# MCU.net
KiCad netlist of a schematic drawn in Altium Designer
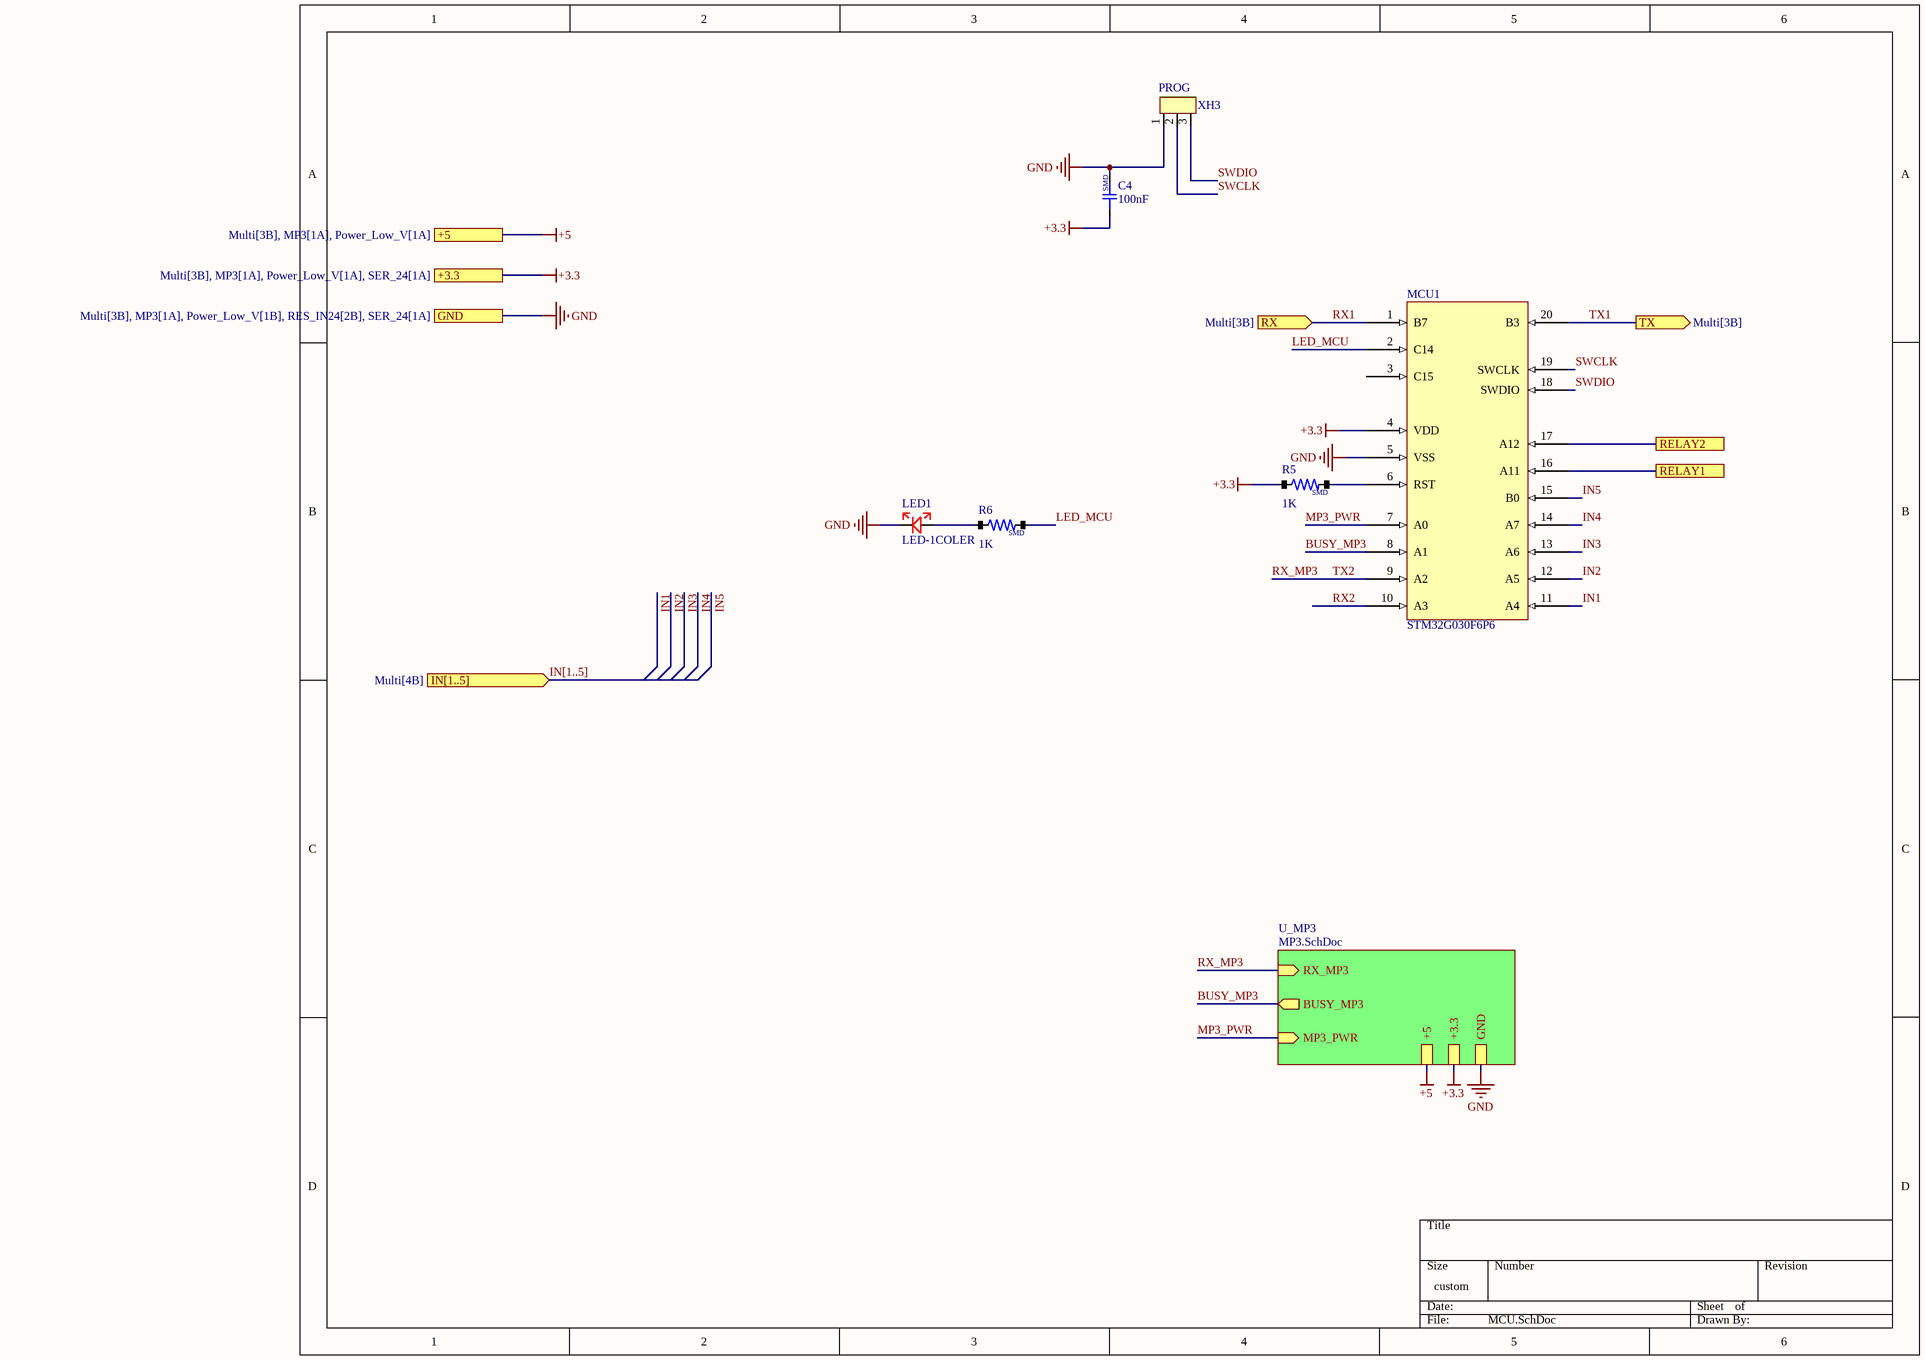
[diagram p0: MCU.SchDoc]

(export (version "E")
  (design (tool "Eeschema 10.0.6"))
  (components
    (comp (ref "C4") (value "100nF") (footprint "CAP-0603") (libsource (lib "kave-eng-pro") (part "cap_smd")))
    (comp (ref "LED1")
      (value "LED-1COLER")
      (footprint "LED/0805")
      (libsource (lib "kave-eng-pro") (part "LED-1COLER"))
    )
    (comp (ref "MCU1")
      (value "STM32G030F6P6")
      (footprint "stm32G030F6P6")
      (libsource (lib "kave-eng-pro") (part "STM32G030F6P6"))
    )
    (comp (ref "PROG") (value "XH3") (footprint "XH3") (libsource (lib "kave-eng-pro") (part "XH3")))
    (comp (ref "R5") (value "1K") (footprint "RES/0603") (libsource (lib "kave-eng-pro") (part "RES/SMD")))
    (comp (ref "R6") (value "1K") (footprint "RES/0603") (libsource (lib "kave-eng-pro") (part "RES/SMD")))
  )
  (nets
    (net (code "1") (name "+3.3") (class "Default")
      (node (ref "C4") (pin "1") (pintype "passive"))
      (node (ref "MCU1") (pin "4") (pinfunction "VDD_4") (pintype "input"))
      (node (ref "R5") (pin "1") (pinfunction "1_1") (pintype "passive"))
    )
    (net (code "3") (name "/BUSY_MP3") (class "Default")
      (node (ref "MCU1") (pin "8") (pinfunction "A1_8") (pintype "input"))
    )
    (net (code "4") (name "/IN1") (class "Default")
      (node (ref "MCU1") (pin "11") (pinfunction "A4_11") (pintype "input"))
    )
    (net (code "5") (name "/IN2") (class "Default")
      (node (ref "MCU1") (pin "12") (pinfunction "A5_12") (pintype "input"))
    )
    (net (code "6") (name "/IN3") (class "Default")
      (node (ref "MCU1") (pin "13") (pinfunction "A6_13") (pintype "input"))
    )
    (net (code "7") (name "/IN4") (class "Default")
      (node (ref "MCU1") (pin "14") (pinfunction "A7_14") (pintype "input"))
    )
    (net (code "8") (name "/IN5") (class "Default")
      (node (ref "MCU1") (pin "15") (pinfunction "B0_15") (pintype "input"))
    )
    (net (code "10") (name "/LED_MCU") (class "Default")
      (node (ref "MCU1") (pin "2") (pinfunction "C14_2") (pintype "input"))
      (node (ref "R6") (pin "2") (pinfunction "2_2") (pintype "passive"))
    )
    (net (code "11") (name "/MP3_PWR") (class "Default")
      (node (ref "MCU1") (pin "7") (pinfunction "A0_7") (pintype "input"))
    )
    (net (code "12") (name "/RELAY1") (class "Default")
      (node (ref "MCU1") (pin "16") (pinfunction "A11_16") (pintype "input"))
    )
    (net (code "13") (name "/RELAY2") (class "Default")
      (node (ref "MCU1") (pin "17") (pinfunction "A12_17") (pintype "input"))
    )
    (net (code "14") (name "/RX1") (class "Default")
      (node (ref "MCU1") (pin "1") (pinfunction "B7_1") (pintype "input"))
    )
    (net (code "15") (name "/RX2") (class "Default")
      (node (ref "MCU1") (pin "10") (pinfunction "A3_10") (pintype "input"))
    )
    (net (code "16") (name "/RX_MP3") (class "Default")
      (node (ref "MCU1") (pin "9") (pinfunction "A2_9") (pintype "input"))
    )
    (net (code "17") (name "/SWCLK") (class "Default")
      (node (ref "MCU1") (pin "19") (pinfunction "SWCLK_19") (pintype "input"))
      (node (ref "PROG") (pin "2") (pintype "open_collector"))
    )
    (net (code "18") (name "/SWDIO") (class "Default")
      (node (ref "MCU1") (pin "18") (pinfunction "SWDIO_18") (pintype "input"))
      (node (ref "PROG") (pin "3") (pintype "open_collector"))
    )
    (net (code "19") (name "/TX1") (class "Default")
      (node (ref "MCU1") (pin "20") (pinfunction "B3_20") (pintype "input"))
    )
    (net (code "20") (name "GND") (class "Default")
      (node (ref "C4") (pin "2") (pintype "passive"))
      (node (ref "LED1") (pin "K") (pintype "passive"))
      (node (ref "MCU1") (pin "5") (pinfunction "VSS_5") (pintype "input"))
      (node (ref "PROG") (pin "1") (pintype "open_collector"))
    )
    (net (code "21") (name "Net-(LED1-PadA)") (class "Default")
      (node (ref "LED1") (pin "A") (pintype "passive"))
      (node (ref "R6") (pin "1") (pinfunction "1_1") (pintype "passive"))
    )
    (net (code "22") (name "Net-(MCU1-RST)") (class "Default")
      (node (ref "MCU1") (pin "6") (pinfunction "RST_6") (pintype "input"))
      (node (ref "R5") (pin "2") (pinfunction "2_2") (pintype "passive"))
    )
    (net (code "23") (name "unconnected-(MCU1-C15-Pad3)") (class "Default")
      (node (ref "MCU1") (pin "3") (pinfunction "C15_3") (pintype "input"))
    )
  )
)
